# DB_MotherBoardConnectors.net
KiCad netlist of a schematic drawn in Altium Designer
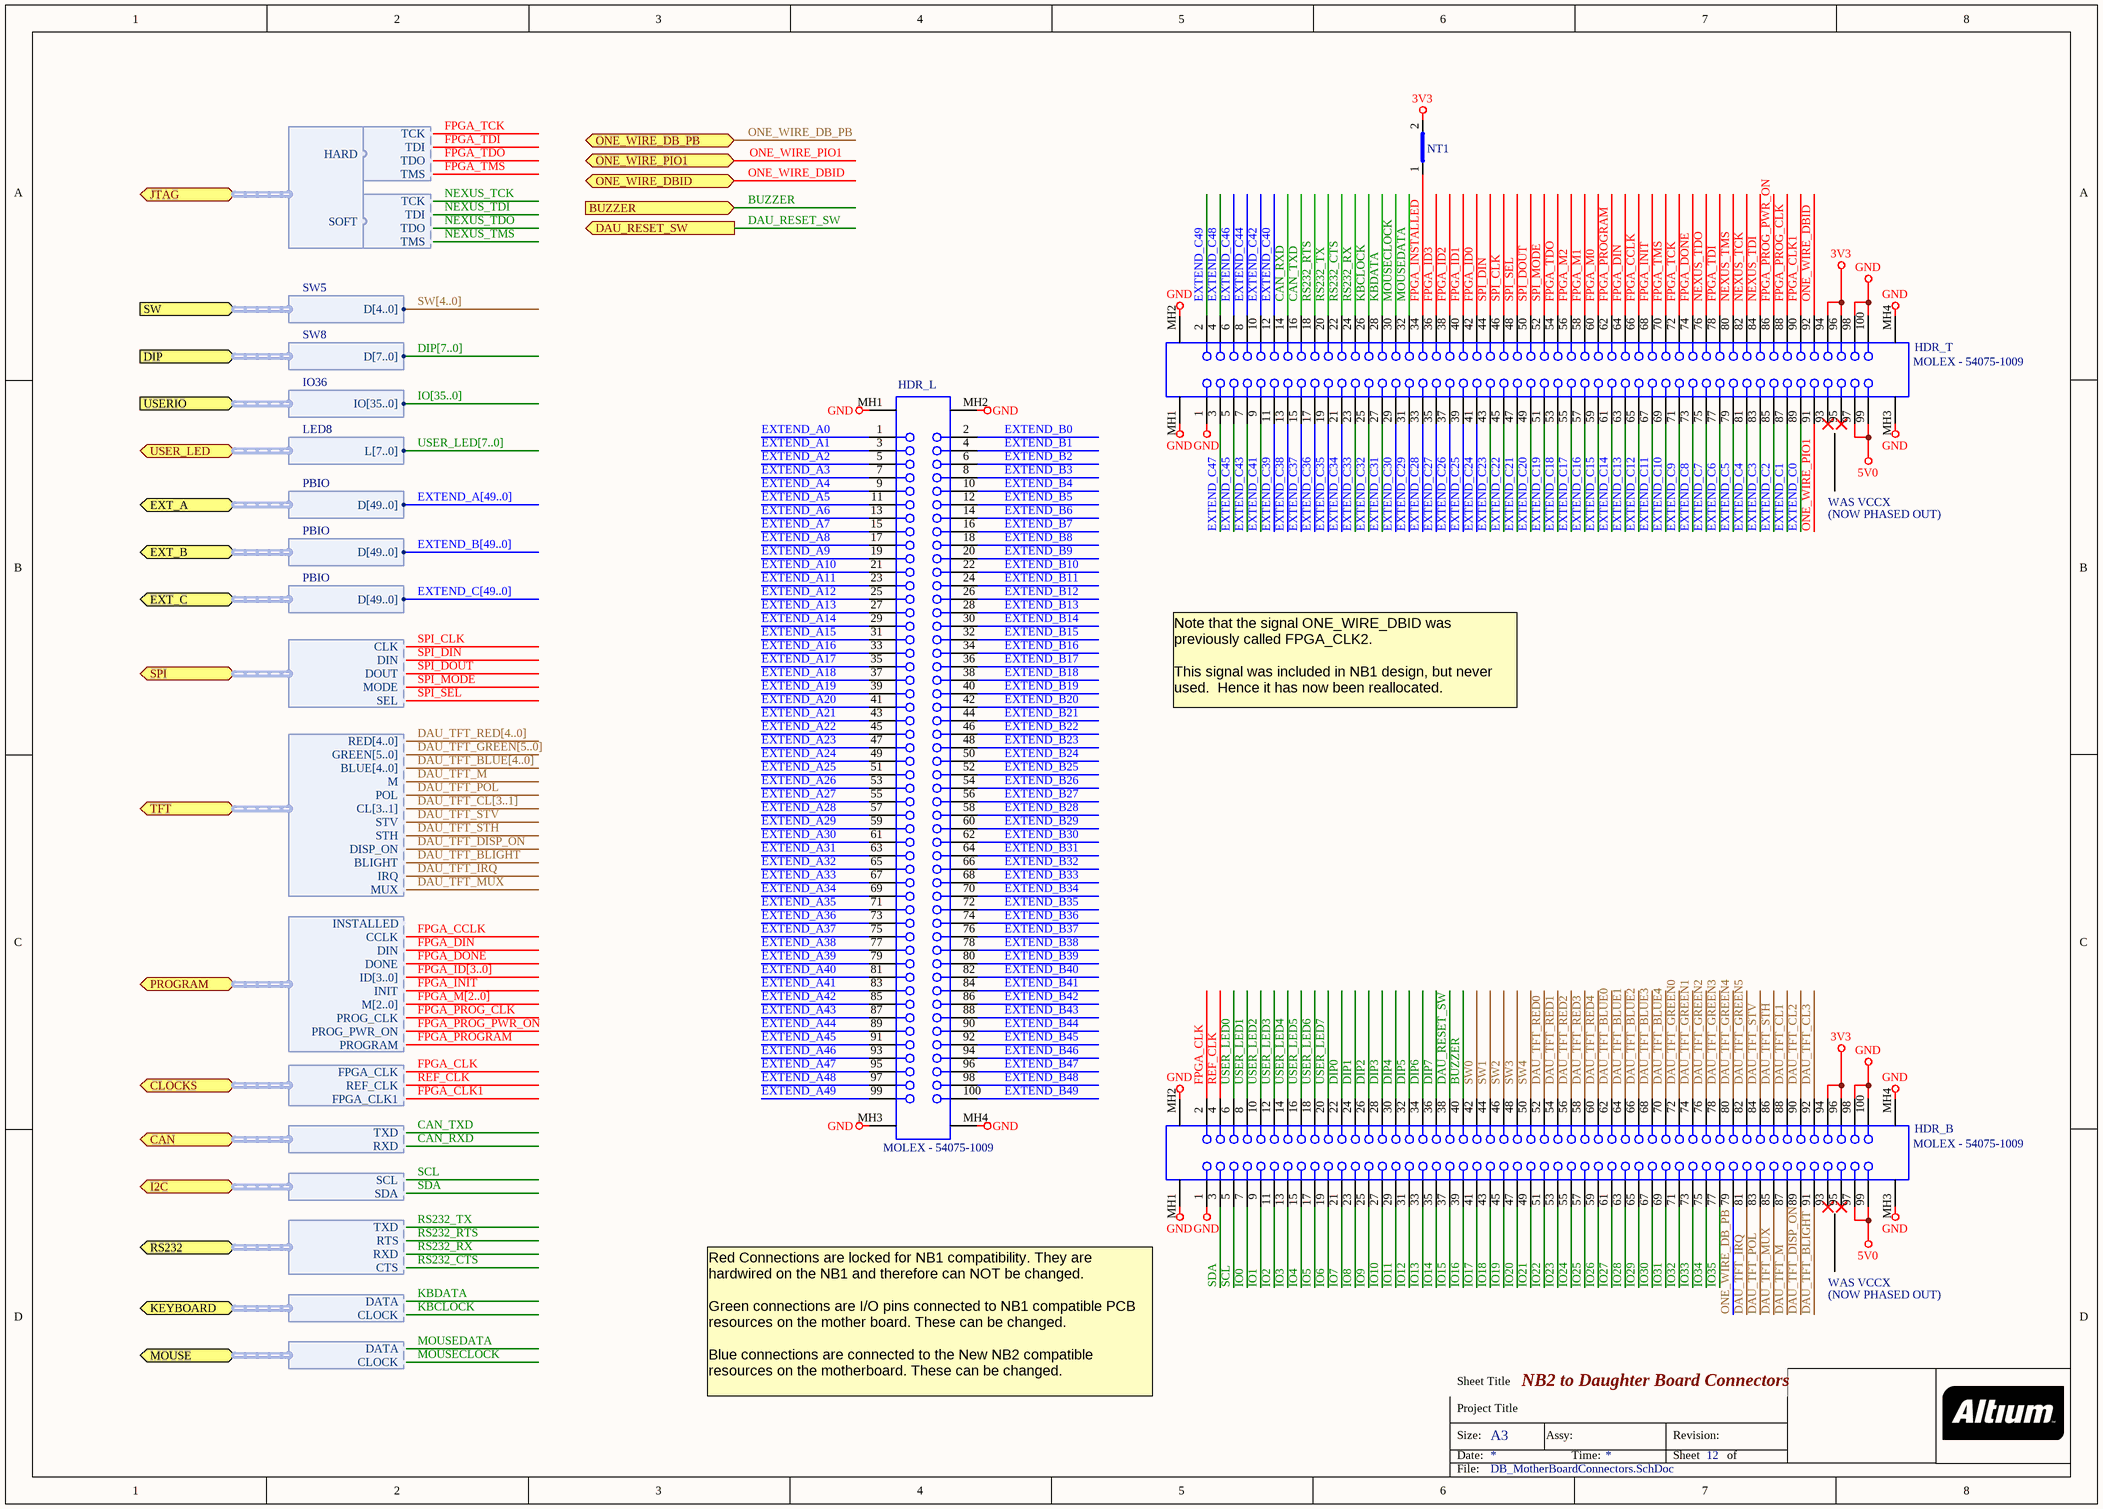
[diagram p0: DB_MotherBoardConnectors.SchDoc]

(export (version "E")
  (design (tool "Eeschema 10.0.6"))
  (components
    (comp (ref "HDR_B")
      (value "MOLEX - 54075-1009")
      (footprint "54075")
      (description "Connector, Molex Docking Station 100 Pin Male 54075")
      (libsource (lib "AltiumDesignLibrary") (part "CON-DOCKSTAT-100-M-STR"))
    )
    (comp (ref "HDR_L")
      (value "MOLEX - 54075-1009")
      (footprint "54075")
      (description "Connector, Molex Docking Station 100 Pin Male 54075")
      (libsource (lib "AltiumDesignLibrary") (part "CON-DOCKSTAT-100-M-STR"))
    )
    (comp (ref "HDR_T")
      (value "MOLEX - 54075-1009")
      (footprint "54075")
      (description "Connector, Molex Docking Station 100 Pin Male 54075")
      (libsource (lib "AltiumDesignLibrary") (part "CON-DOCKSTAT-100-M-STR"))
    )
    (comp (ref "NT1")
      (value "Net Tie SMT2")
      (footprint "NETTIE-SMT2-8X8")
      (description "Net-Tie, Surface Mount, 2 x 0.4mm x 0.2mm SMT Pads - For 0.2mm Track")
      (libsource (lib "AltiumDesignLibrary") (part "NETTIE-SMT2"))
    )
  )
  (nets
    (net (code "17") (name "/BUZZER") (class "Default")
      (node (ref "HDR_B") (pin "40") (pinfunction "40_40") (pintype "passive"))
    )
    (net (code "18") (name "/CAN_RXD") (class "Default")
      (node (ref "HDR_T") (pin "14") (pinfunction "14_14") (pintype "passive"))
    )
    (net (code "19") (name "/CAN_TXD") (class "Default")
      (node (ref "HDR_T") (pin "16") (pinfunction "16_16") (pintype "passive"))
    )
    (net (code "20") (name "/DAU_RESET_SW") (class "Default")
      (node (ref "HDR_B") (pin "38") (pinfunction "38_38") (pintype "passive"))
    )
    (net (code "21") (name "/DAU_TFT_BLIGHT") (class "Default")
      (node (ref "HDR_B") (pin "91") (pinfunction "91_91") (pintype "passive"))
    )
    (net (code "22") (name "/DAU_TFT_BLUE0") (class "Default")
      (node (ref "HDR_B") (pin "62") (pinfunction "62_62") (pintype "passive"))
    )
    (net (code "23") (name "/DAU_TFT_BLUE1") (class "Default")
      (node (ref "HDR_B") (pin "64") (pinfunction "64_64") (pintype "passive"))
    )
    (net (code "24") (name "/DAU_TFT_BLUE2") (class "Default")
      (node (ref "HDR_B") (pin "66") (pinfunction "66_66") (pintype "passive"))
    )
    (net (code "25") (name "/DAU_TFT_BLUE3") (class "Default")
      (node (ref "HDR_B") (pin "68") (pinfunction "68_68") (pintype "passive"))
    )
    (net (code "26") (name "/DAU_TFT_BLUE4") (class "Default")
      (node (ref "HDR_B") (pin "70") (pinfunction "70_70") (pintype "passive"))
    )
    (net (code "28") (name "/DAU_TFT_CL1") (class "Default")
      (node (ref "HDR_B") (pin "88") (pinfunction "88_88") (pintype "passive"))
    )
    (net (code "29") (name "/DAU_TFT_CL2") (class "Default")
      (node (ref "HDR_B") (pin "90") (pinfunction "90_90") (pintype "passive"))
    )
    (net (code "30") (name "/DAU_TFT_CL3") (class "Default")
      (node (ref "HDR_B") (pin "92") (pinfunction "92_92") (pintype "passive"))
    )
    (net (code "32") (name "/DAU_TFT_DISP_ON") (class "Default")
      (node (ref "HDR_B") (pin "89") (pinfunction "89_89") (pintype "passive"))
    )
    (net (code "33") (name "/DAU_TFT_GREEN0") (class "Default")
      (node (ref "HDR_B") (pin "72") (pinfunction "72_72") (pintype "passive"))
    )
    (net (code "34") (name "/DAU_TFT_GREEN1") (class "Default")
      (node (ref "HDR_B") (pin "74") (pinfunction "74_74") (pintype "passive"))
    )
    (net (code "35") (name "/DAU_TFT_GREEN2") (class "Default")
      (node (ref "HDR_B") (pin "76") (pinfunction "76_76") (pintype "passive"))
    )
    (net (code "36") (name "/DAU_TFT_GREEN3") (class "Default")
      (node (ref "HDR_B") (pin "78") (pinfunction "78_78") (pintype "passive"))
    )
    (net (code "37") (name "/DAU_TFT_GREEN4") (class "Default")
      (node (ref "HDR_B") (pin "80") (pinfunction "80_80") (pintype "passive"))
    )
    (net (code "38") (name "/DAU_TFT_GREEN5") (class "Default")
      (node (ref "HDR_B") (pin "82") (pinfunction "82_82") (pintype "passive"))
    )
    (net (code "40") (name "/DAU_TFT_IRQ") (class "Default")
      (node (ref "HDR_B") (pin "81") (pinfunction "81_81") (pintype "passive"))
    )
    (net (code "41") (name "/DAU_TFT_M") (class "Default")
      (node (ref "HDR_B") (pin "87") (pinfunction "87_87") (pintype "passive"))
    )
    (net (code "42") (name "/DAU_TFT_MUX") (class "Default")
      (node (ref "HDR_B") (pin "85") (pinfunction "85_85") (pintype "passive"))
    )
    (net (code "43") (name "/DAU_TFT_POL") (class "Default")
      (node (ref "HDR_B") (pin "83") (pinfunction "83_83") (pintype "passive"))
    )
    (net (code "44") (name "/DAU_TFT_RED0") (class "Default")
      (node (ref "HDR_B") (pin "52") (pinfunction "52_52") (pintype "passive"))
    )
    (net (code "45") (name "/DAU_TFT_RED1") (class "Default")
      (node (ref "HDR_B") (pin "54") (pinfunction "54_54") (pintype "passive"))
    )
    (net (code "46") (name "/DAU_TFT_RED2") (class "Default")
      (node (ref "HDR_B") (pin "56") (pinfunction "56_56") (pintype "passive"))
    )
    (net (code "47") (name "/DAU_TFT_RED3") (class "Default")
      (node (ref "HDR_B") (pin "58") (pinfunction "58_58") (pintype "passive"))
    )
    (net (code "48") (name "/DAU_TFT_RED4") (class "Default")
      (node (ref "HDR_B") (pin "60") (pinfunction "60_60") (pintype "passive"))
    )
    (net (code "50") (name "/DAU_TFT_STH") (class "Default")
      (node (ref "HDR_B") (pin "86") (pinfunction "86_86") (pintype "passive"))
    )
    (net (code "51") (name "/DAU_TFT_STV") (class "Default")
      (node (ref "HDR_B") (pin "84") (pinfunction "84_84") (pintype "passive"))
    )
    (net (code "52") (name "/DIP0") (class "Default")
      (node (ref "HDR_B") (pin "22") (pinfunction "22_22") (pintype "passive"))
    )
    (net (code "53") (name "/DIP1") (class "Default")
      (node (ref "HDR_B") (pin "24") (pinfunction "24_24") (pintype "passive"))
    )
    (net (code "54") (name "/DIP2") (class "Default")
      (node (ref "HDR_B") (pin "26") (pinfunction "26_26") (pintype "passive"))
    )
    (net (code "55") (name "/DIP3") (class "Default")
      (node (ref "HDR_B") (pin "28") (pinfunction "28_28") (pintype "passive"))
    )
    (net (code "56") (name "/DIP4") (class "Default")
      (node (ref "HDR_B") (pin "30") (pinfunction "30_30") (pintype "passive"))
    )
    (net (code "57") (name "/DIP5") (class "Default")
      (node (ref "HDR_B") (pin "32") (pinfunction "32_32") (pintype "passive"))
    )
    (net (code "58") (name "/DIP6") (class "Default")
      (node (ref "HDR_B") (pin "34") (pinfunction "34_34") (pintype "passive"))
    )
    (net (code "59") (name "/DIP7") (class "Default")
      (node (ref "HDR_B") (pin "36") (pinfunction "36_36") (pintype "passive"))
    )
    (net (code "61") (name "/EXTEND_A0") (class "Default")
      (node (ref "HDR_L") (pin "1") (pinfunction "1_1") (pintype "passive"))
    )
    (net (code "62") (name "/EXTEND_A1") (class "Default")
      (node (ref "HDR_L") (pin "3") (pinfunction "3_3") (pintype "passive"))
    )
    (net (code "63") (name "/EXTEND_A2") (class "Default")
      (node (ref "HDR_L") (pin "5") (pinfunction "5_5") (pintype "passive"))
    )
    (net (code "64") (name "/EXTEND_A3") (class "Default")
      (node (ref "HDR_L") (pin "7") (pinfunction "7_7") (pintype "passive"))
    )
    (net (code "65") (name "/EXTEND_A4") (class "Default")
      (node (ref "HDR_L") (pin "9") (pinfunction "9_9") (pintype "passive"))
    )
    (net (code "66") (name "/EXTEND_A5") (class "Default")
      (node (ref "HDR_L") (pin "11") (pinfunction "11_11") (pintype "passive"))
    )
    (net (code "67") (name "/EXTEND_A6") (class "Default")
      (node (ref "HDR_L") (pin "13") (pinfunction "13_13") (pintype "passive"))
    )
    (net (code "68") (name "/EXTEND_A7") (class "Default")
      (node (ref "HDR_L") (pin "15") (pinfunction "15_15") (pintype "passive"))
    )
    (net (code "69") (name "/EXTEND_A8") (class "Default")
      (node (ref "HDR_L") (pin "17") (pinfunction "17_17") (pintype "passive"))
    )
    (net (code "70") (name "/EXTEND_A9") (class "Default")
      (node (ref "HDR_L") (pin "19") (pinfunction "19_19") (pintype "passive"))
    )
    (net (code "71") (name "/EXTEND_A10") (class "Default")
      (node (ref "HDR_L") (pin "21") (pinfunction "21_21") (pintype "passive"))
    )
    (net (code "72") (name "/EXTEND_A11") (class "Default")
      (node (ref "HDR_L") (pin "23") (pinfunction "23_23") (pintype "passive"))
    )
    (net (code "73") (name "/EXTEND_A12") (class "Default")
      (node (ref "HDR_L") (pin "25") (pinfunction "25_25") (pintype "passive"))
    )
    (net (code "74") (name "/EXTEND_A13") (class "Default")
      (node (ref "HDR_L") (pin "27") (pinfunction "27_27") (pintype "passive"))
    )
    (net (code "75") (name "/EXTEND_A14") (class "Default")
      (node (ref "HDR_L") (pin "29") (pinfunction "29_29") (pintype "passive"))
    )
    (net (code "76") (name "/EXTEND_A15") (class "Default")
      (node (ref "HDR_L") (pin "31") (pinfunction "31_31") (pintype "passive"))
    )
    (net (code "77") (name "/EXTEND_A16") (class "Default")
      (node (ref "HDR_L") (pin "33") (pinfunction "33_33") (pintype "passive"))
    )
    (net (code "78") (name "/EXTEND_A17") (class "Default")
      (node (ref "HDR_L") (pin "35") (pinfunction "35_35") (pintype "passive"))
    )
    (net (code "79") (name "/EXTEND_A18") (class "Default")
      (node (ref "HDR_L") (pin "37") (pinfunction "37_37") (pintype "passive"))
    )
    (net (code "80") (name "/EXTEND_A19") (class "Default")
      (node (ref "HDR_L") (pin "39") (pinfunction "39_39") (pintype "passive"))
    )
    (net (code "81") (name "/EXTEND_A20") (class "Default")
      (node (ref "HDR_L") (pin "41") (pinfunction "41_41") (pintype "passive"))
    )
    (net (code "82") (name "/EXTEND_A21") (class "Default")
      (node (ref "HDR_L") (pin "43") (pinfunction "43_43") (pintype "passive"))
    )
    (net (code "83") (name "/EXTEND_A22") (class "Default")
      (node (ref "HDR_L") (pin "45") (pinfunction "45_45") (pintype "passive"))
    )
    (net (code "84") (name "/EXTEND_A23") (class "Default")
      (node (ref "HDR_L") (pin "47") (pinfunction "47_47") (pintype "passive"))
    )
    (net (code "85") (name "/EXTEND_A24") (class "Default")
      (node (ref "HDR_L") (pin "49") (pinfunction "49_49") (pintype "passive"))
    )
    (net (code "86") (name "/EXTEND_A25") (class "Default")
      (node (ref "HDR_L") (pin "51") (pinfunction "51_51") (pintype "passive"))
    )
    (net (code "87") (name "/EXTEND_A26") (class "Default")
      (node (ref "HDR_L") (pin "53") (pinfunction "53_53") (pintype "passive"))
    )
    (net (code "88") (name "/EXTEND_A27") (class "Default")
      (node (ref "HDR_L") (pin "55") (pinfunction "55_55") (pintype "passive"))
    )
    (net (code "89") (name "/EXTEND_A28") (class "Default")
      (node (ref "HDR_L") (pin "57") (pinfunction "57_57") (pintype "passive"))
    )
    (net (code "90") (name "/EXTEND_A29") (class "Default")
      (node (ref "HDR_L") (pin "59") (pinfunction "59_59") (pintype "passive"))
    )
    (net (code "91") (name "/EXTEND_A30") (class "Default")
      (node (ref "HDR_L") (pin "61") (pinfunction "61_61") (pintype "passive"))
    )
    (net (code "92") (name "/EXTEND_A31") (class "Default")
      (node (ref "HDR_L") (pin "63") (pinfunction "63_63") (pintype "passive"))
    )
    (net (code "93") (name "/EXTEND_A32") (class "Default")
      (node (ref "HDR_L") (pin "65") (pinfunction "65_65") (pintype "passive"))
    )
    (net (code "94") (name "/EXTEND_A33") (class "Default")
      (node (ref "HDR_L") (pin "67") (pinfunction "67_67") (pintype "passive"))
    )
    (net (code "95") (name "/EXTEND_A34") (class "Default")
      (node (ref "HDR_L") (pin "69") (pinfunction "69_69") (pintype "passive"))
    )
    (net (code "96") (name "/EXTEND_A35") (class "Default")
      (node (ref "HDR_L") (pin "71") (pinfunction "71_71") (pintype "passive"))
    )
    (net (code "97") (name "/EXTEND_A36") (class "Default")
      (node (ref "HDR_L") (pin "73") (pinfunction "73_73") (pintype "passive"))
    )
    (net (code "98") (name "/EXTEND_A37") (class "Default")
      (node (ref "HDR_L") (pin "75") (pinfunction "75_75") (pintype "passive"))
    )
    (net (code "99") (name "/EXTEND_A38") (class "Default")
      (node (ref "HDR_L") (pin "77") (pinfunction "77_77") (pintype "passive"))
    )
    (net (code "100") (name "/EXTEND_A39") (class "Default")
      (node (ref "HDR_L") (pin "79") (pinfunction "79_79") (pintype "passive"))
    )
    (net (code "101") (name "/EXTEND_A40") (class "Default")
      (node (ref "HDR_L") (pin "81") (pinfunction "81_81") (pintype "passive"))
    )
    (net (code "102") (name "/EXTEND_A41") (class "Default")
      (node (ref "HDR_L") (pin "83") (pinfunction "83_83") (pintype "passive"))
    )
    (net (code "103") (name "/EXTEND_A42") (class "Default")
      (node (ref "HDR_L") (pin "85") (pinfunction "85_85") (pintype "passive"))
    )
    (net (code "104") (name "/EXTEND_A43") (class "Default")
      (node (ref "HDR_L") (pin "87") (pinfunction "87_87") (pintype "passive"))
    )
    (net (code "105") (name "/EXTEND_A44") (class "Default")
      (node (ref "HDR_L") (pin "89") (pinfunction "89_89") (pintype "passive"))
    )
    (net (code "106") (name "/EXTEND_A45") (class "Default")
      (node (ref "HDR_L") (pin "91") (pinfunction "91_91") (pintype "passive"))
    )
    (net (code "107") (name "/EXTEND_A46") (class "Default")
      (node (ref "HDR_L") (pin "93") (pinfunction "93_93") (pintype "passive"))
    )
    (net (code "108") (name "/EXTEND_A47") (class "Default")
      (node (ref "HDR_L") (pin "95") (pinfunction "95_95") (pintype "passive"))
    )
    (net (code "109") (name "/EXTEND_A48") (class "Default")
      (node (ref "HDR_L") (pin "97") (pinfunction "97_97") (pintype "passive"))
    )
    (net (code "110") (name "/EXTEND_A49") (class "Default")
      (node (ref "HDR_L") (pin "99") (pinfunction "99_99") (pintype "passive"))
    )
    (net (code "111") (name "/EXTEND_B0") (class "Default")
      (node (ref "HDR_L") (pin "2") (pinfunction "2_2") (pintype "passive"))
    )
    (net (code "112") (name "/EXTEND_B1") (class "Default")
      (node (ref "HDR_L") (pin "4") (pinfunction "4_4") (pintype "passive"))
    )
    (net (code "113") (name "/EXTEND_B2") (class "Default")
      (node (ref "HDR_L") (pin "6") (pinfunction "6_6") (pintype "passive"))
    )
    (net (code "114") (name "/EXTEND_B3") (class "Default")
      (node (ref "HDR_L") (pin "8") (pinfunction "8_8") (pintype "passive"))
    )
    (net (code "115") (name "/EXTEND_B4") (class "Default")
      (node (ref "HDR_L") (pin "10") (pinfunction "10_10") (pintype "passive"))
    )
    (net (code "116") (name "/EXTEND_B5") (class "Default")
      (node (ref "HDR_L") (pin "12") (pinfunction "12_12") (pintype "passive"))
    )
    (net (code "117") (name "/EXTEND_B6") (class "Default")
      (node (ref "HDR_L") (pin "14") (pinfunction "14_14") (pintype "passive"))
    )
    (net (code "118") (name "/EXTEND_B7") (class "Default")
      (node (ref "HDR_L") (pin "16") (pinfunction "16_16") (pintype "passive"))
    )
    (net (code "119") (name "/EXTEND_B8") (class "Default")
      (node (ref "HDR_L") (pin "18") (pinfunction "18_18") (pintype "passive"))
    )
    (net (code "120") (name "/EXTEND_B9") (class "Default")
      (node (ref "HDR_L") (pin "20") (pinfunction "20_20") (pintype "passive"))
    )
    (net (code "121") (name "/EXTEND_B10") (class "Default")
      (node (ref "HDR_L") (pin "22") (pinfunction "22_22") (pintype "passive"))
    )
    (net (code "122") (name "/EXTEND_B11") (class "Default")
      (node (ref "HDR_L") (pin "24") (pinfunction "24_24") (pintype "passive"))
    )
    (net (code "123") (name "/EXTEND_B12") (class "Default")
      (node (ref "HDR_L") (pin "26") (pinfunction "26_26") (pintype "passive"))
    )
    (net (code "124") (name "/EXTEND_B13") (class "Default")
      (node (ref "HDR_L") (pin "28") (pinfunction "28_28") (pintype "passive"))
    )
    (net (code "125") (name "/EXTEND_B14") (class "Default")
      (node (ref "HDR_L") (pin "30") (pinfunction "30_30") (pintype "passive"))
    )
    (net (code "126") (name "/EXTEND_B15") (class "Default")
      (node (ref "HDR_L") (pin "32") (pinfunction "32_32") (pintype "passive"))
    )
    (net (code "127") (name "/EXTEND_B16") (class "Default")
      (node (ref "HDR_L") (pin "34") (pinfunction "34_34") (pintype "passive"))
    )
    (net (code "128") (name "/EXTEND_B17") (class "Default")
      (node (ref "HDR_L") (pin "36") (pinfunction "36_36") (pintype "passive"))
    )
    (net (code "129") (name "/EXTEND_B18") (class "Default")
      (node (ref "HDR_L") (pin "38") (pinfunction "38_38") (pintype "passive"))
    )
    (net (code "130") (name "/EXTEND_B19") (class "Default")
      (node (ref "HDR_L") (pin "40") (pinfunction "40_40") (pintype "passive"))
    )
    (net (code "131") (name "/EXTEND_B20") (class "Default")
      (node (ref "HDR_L") (pin "42") (pinfunction "42_42") (pintype "passive"))
    )
    (net (code "132") (name "/EXTEND_B21") (class "Default")
      (node (ref "HDR_L") (pin "44") (pinfunction "44_44") (pintype "passive"))
    )
    (net (code "133") (name "/EXTEND_B22") (class "Default")
      (node (ref "HDR_L") (pin "46") (pinfunction "46_46") (pintype "passive"))
    )
    (net (code "134") (name "/EXTEND_B23") (class "Default")
      (node (ref "HDR_L") (pin "48") (pinfunction "48_48") (pintype "passive"))
    )
    (net (code "135") (name "/EXTEND_B24") (class "Default")
      (node (ref "HDR_L") (pin "50") (pinfunction "50_50") (pintype "passive"))
    )
    (net (code "136") (name "/EXTEND_B25") (class "Default")
      (node (ref "HDR_L") (pin "52") (pinfunction "52_52") (pintype "passive"))
    )
    (net (code "137") (name "/EXTEND_B26") (class "Default")
      (node (ref "HDR_L") (pin "54") (pinfunction "54_54") (pintype "passive"))
    )
    (net (code "138") (name "/EXTEND_B27") (class "Default")
      (node (ref "HDR_L") (pin "56") (pinfunction "56_56") (pintype "passive"))
    )
    (net (code "139") (name "/EXTEND_B28") (class "Default")
      (node (ref "HDR_L") (pin "58") (pinfunction "58_58") (pintype "passive"))
    )
    (net (code "140") (name "/EXTEND_B29") (class "Default")
      (node (ref "HDR_L") (pin "60") (pinfunction "60_60") (pintype "passive"))
    )
    (net (code "141") (name "/EXTEND_B30") (class "Default")
      (node (ref "HDR_L") (pin "62") (pinfunction "62_62") (pintype "passive"))
    )
    (net (code "142") (name "/EXTEND_B31") (class "Default")
      (node (ref "HDR_L") (pin "64") (pinfunction "64_64") (pintype "passive"))
    )
    (net (code "143") (name "/EXTEND_B32") (class "Default")
      (node (ref "HDR_L") (pin "66") (pinfunction "66_66") (pintype "passive"))
    )
    (net (code "144") (name "/EXTEND_B33") (class "Default")
      (node (ref "HDR_L") (pin "68") (pinfunction "68_68") (pintype "passive"))
    )
    (net (code "145") (name "/EXTEND_B34") (class "Default")
      (node (ref "HDR_L") (pin "70") (pinfunction "70_70") (pintype "passive"))
    )
    (net (code "146") (name "/EXTEND_B35") (class "Default")
      (node (ref "HDR_L") (pin "72") (pinfunction "72_72") (pintype "passive"))
    )
    (net (code "147") (name "/EXTEND_B36") (class "Default")
      (node (ref "HDR_L") (pin "74") (pinfunction "74_74") (pintype "passive"))
    )
    (net (code "148") (name "/EXTEND_B37") (class "Default")
      (node (ref "HDR_L") (pin "76") (pinfunction "76_76") (pintype "passive"))
    )
    (net (code "149") (name "/EXTEND_B38") (class "Default")
      (node (ref "HDR_L") (pin "78") (pinfunction "78_78") (pintype "passive"))
    )
    (net (code "150") (name "/EXTEND_B39") (class "Default")
      (node (ref "HDR_L") (pin "80") (pinfunction "80_80") (pintype "passive"))
    )
    (net (code "151") (name "/EXTEND_B40") (class "Default")
      (node (ref "HDR_L") (pin "82") (pinfunction "82_82") (pintype "passive"))
    )
    (net (code "152") (name "/EXTEND_B41") (class "Default")
      (node (ref "HDR_L") (pin "84") (pinfunction "84_84") (pintype "passive"))
    )
    (net (code "153") (name "/EXTEND_B42") (class "Default")
      (node (ref "HDR_L") (pin "86") (pinfunction "86_86") (pintype "passive"))
    )
    (net (code "154") (name "/EXTEND_B43") (class "Default")
      (node (ref "HDR_L") (pin "88") (pinfunction "88_88") (pintype "passive"))
    )
    (net (code "155") (name "/EXTEND_B44") (class "Default")
      (node (ref "HDR_L") (pin "90") (pinfunction "90_90") (pintype "passive"))
    )
    (net (code "156") (name "/EXTEND_B45") (class "Default")
      (node (ref "HDR_L") (pin "92") (pinfunction "92_92") (pintype "passive"))
    )
    (net (code "157") (name "/EXTEND_B46") (class "Default")
      (node (ref "HDR_L") (pin "94") (pinfunction "94_94") (pintype "passive"))
    )
    (net (code "158") (name "/EXTEND_B47") (class "Default")
      (node (ref "HDR_L") (pin "96") (pinfunction "96_96") (pintype "passive"))
    )
    (net (code "159") (name "/EXTEND_B48") (class "Default")
      (node (ref "HDR_L") (pin "98") (pinfunction "98_98") (pintype "passive"))
    )
    (net (code "160") (name "/EXTEND_B49") (class "Default")
      (node (ref "HDR_L") (pin "100") (pinfunction "100_100") (pintype "passive"))
    )
    (net (code "161") (name "/EXTEND_C0") (class "Default")
      (node (ref "HDR_T") (pin "89") (pinfunction "89_89") (pintype "passive"))
    )
    (net (code "162") (name "/EXTEND_C1") (class "Default")
      (node (ref "HDR_T") (pin "87") (pinfunction "87_87") (pintype "passive"))
    )
    (net (code "163") (name "/EXTEND_C2") (class "Default")
      (node (ref "HDR_T") (pin "85") (pinfunction "85_85") (pintype "passive"))
    )
    (net (code "164") (name "/EXTEND_C3") (class "Default")
      (node (ref "HDR_T") (pin "83") (pinfunction "83_83") (pintype "passive"))
    )
    (net (code "165") (name "/EXTEND_C4") (class "Default")
      (node (ref "HDR_T") (pin "81") (pinfunction "81_81") (pintype "passive"))
    )
    (net (code "166") (name "/EXTEND_C5") (class "Default")
      (node (ref "HDR_T") (pin "79") (pinfunction "79_79") (pintype "passive"))
    )
    (net (code "167") (name "/EXTEND_C6") (class "Default")
      (node (ref "HDR_T") (pin "77") (pinfunction "77_77") (pintype "passive"))
    )
    (net (code "168") (name "/EXTEND_C7") (class "Default")
      (node (ref "HDR_T") (pin "75") (pinfunction "75_75") (pintype "passive"))
    )
    (net (code "169") (name "/EXTEND_C8") (class "Default")
      (node (ref "HDR_T") (pin "73") (pinfunction "73_73") (pintype "passive"))
    )
    (net (code "170") (name "/EXTEND_C9") (class "Default")
      (node (ref "HDR_T") (pin "71") (pinfunction "71_71") (pintype "passive"))
    )
    (net (code "171") (name "/EXTEND_C10") (class "Default")
      (node (ref "HDR_T") (pin "69") (pinfunction "69_69") (pintype "passive"))
    )
    (net (code "172") (name "/EXTEND_C11") (class "Default")
      (node (ref "HDR_T") (pin "67") (pinfunction "67_67") (pintype "passive"))
    )
    (net (code "173") (name "/EXTEND_C12") (class "Default")
      (node (ref "HDR_T") (pin "65") (pinfunction "65_65") (pintype "passive"))
    )
    (net (code "174") (name "/EXTEND_C13") (class "Default")
      (node (ref "HDR_T") (pin "63") (pinfunction "63_63") (pintype "passive"))
    )
    (net (code "175") (name "/EXTEND_C14") (class "Default")
      (node (ref "HDR_T") (pin "61") (pinfunction "61_61") (pintype "passive"))
    )
    (net (code "176") (name "/EXTEND_C15") (class "Default")
      (node (ref "HDR_T") (pin "59") (pinfunction "59_59") (pintype "passive"))
    )
    (net (code "177") (name "/EXTEND_C16") (class "Default")
      (node (ref "HDR_T") (pin "57") (pinfunction "57_57") (pintype "passive"))
    )
    (net (code "178") (name "/EXTEND_C17") (class "Default")
      (node (ref "HDR_T") (pin "55") (pinfunction "55_55") (pintype "passive"))
    )
    (net (code "179") (name "/EXTEND_C18") (class "Default")
      (node (ref "HDR_T") (pin "53") (pinfunction "53_53") (pintype "passive"))
    )
    (net (code "180") (name "/EXTEND_C19") (class "Default")
      (node (ref "HDR_T") (pin "51") (pinfunction "51_51") (pintype "passive"))
    )
    (net (code "181") (name "/EXTEND_C20") (class "Default")
      (node (ref "HDR_T") (pin "49") (pinfunction "49_49") (pintype "passive"))
    )
    (net (code "182") (name "/EXTEND_C21") (class "Default")
      (node (ref "HDR_T") (pin "47") (pinfunction "47_47") (pintype "passive"))
    )
    (net (code "183") (name "/EXTEND_C22") (class "Default")
      (node (ref "HDR_T") (pin "45") (pinfunction "45_45") (pintype "passive"))
    )
    (net (code "184") (name "/EXTEND_C23") (class "Default")
      (node (ref "HDR_T") (pin "43") (pinfunction "43_43") (pintype "passive"))
    )
    (net (code "185") (name "/EXTEND_C24") (class "Default")
      (node (ref "HDR_T") (pin "41") (pinfunction "41_41") (pintype "passive"))
    )
    (net (code "186") (name "/EXTEND_C25") (class "Default")
      (node (ref "HDR_T") (pin "39") (pinfunction "39_39") (pintype "passive"))
    )
    (net (code "187") (name "/EXTEND_C26") (class "Default")
      (node (ref "HDR_T") (pin "37") (pinfunction "37_37") (pintype "passive"))
    )
    (net (code "188") (name "/EXTEND_C27") (class "Default")
      (node (ref "HDR_T") (pin "35") (pinfunction "35_35") (pintype "passive"))
    )
    (net (code "189") (name "/EXTEND_C28") (class "Default")
      (node (ref "HDR_T") (pin "33") (pinfunction "33_33") (pintype "passive"))
    )
    (net (code "190") (name "/EXTEND_C29") (class "Default")
      (node (ref "HDR_T") (pin "31") (pinfunction "31_31") (pintype "passive"))
    )
    (net (code "191") (name "/EXTEND_C30") (class "Default")
      (node (ref "HDR_T") (pin "29") (pinfunction "29_29") (pintype "passive"))
    )
    (net (code "192") (name "/EXTEND_C31") (class "Default")
      (node (ref "HDR_T") (pin "27") (pinfunction "27_27") (pintype "passive"))
    )
    (net (code "193") (name "/EXTEND_C32") (class "Default")
      (node (ref "HDR_T") (pin "25") (pinfunction "25_25") (pintype "passive"))
    )
    (net (code "194") (name "/EXTEND_C33") (class "Default")
      (node (ref "HDR_T") (pin "23") (pinfunction "23_23") (pintype "passive"))
    )
    (net (code "195") (name "/EXTEND_C34") (class "Default")
      (node (ref "HDR_T") (pin "21") (pinfunction "21_21") (pintype "passive"))
    )
    (net (code "196") (name "/EXTEND_C35") (class "Default")
      (node (ref "HDR_T") (pin "19") (pinfunction "19_19") (pintype "passive"))
    )
    (net (code "197") (name "/EXTEND_C36") (class "Default")
      (node (ref "HDR_T") (pin "17") (pinfunction "17_17") (pintype "passive"))
    )
    (net (code "198") (name "/EXTEND_C37") (class "Default")
      (node (ref "HDR_T") (pin "15") (pinfunction "15_15") (pintype "passive"))
    )
    (net (code "199") (name "/EXTEND_C38") (class "Default")
      (node (ref "HDR_T") (pin "13") (pinfunction "13_13") (pintype "passive"))
    )
    (net (code "200") (name "/EXTEND_C39") (class "Default")
      (node (ref "HDR_T") (pin "11") (pinfunction "11_11") (pintype "passive"))
    )
    (net (code "201") (name "/EXTEND_C40") (class "Default")
      (node (ref "HDR_T") (pin "12") (pinfunction "12_12") (pintype "passive"))
    )
    (net (code "202") (name "/EXTEND_C41") (class "Default")
      (node (ref "HDR_T") (pin "9") (pinfunction "9_9") (pintype "passive"))
    )
    (net (code "203") (name "/EXTEND_C42") (class "Default")
      (node (ref "HDR_T") (pin "10") (pinfunction "10_10") (pintype "passive"))
    )
    (net (code "204") (name "/EXTEND_C43") (class "Default")
      (node (ref "HDR_T") (pin "7") (pinfunction "7_7") (pintype "passive"))
    )
    (net (code "205") (name "/EXTEND_C44") (class "Default")
      (node (ref "HDR_T") (pin "8") (pinfunction "8_8") (pintype "passive"))
    )
    (net (code "206") (name "/EXTEND_C45") (class "Default")
      (node (ref "HDR_T") (pin "5") (pinfunction "5_5") (pintype "passive"))
    )
    (net (code "207") (name "/EXTEND_C46") (class "Default")
      (node (ref "HDR_T") (pin "6") (pinfunction "6_6") (pintype "passive"))
    )
    (net (code "208") (name "/EXTEND_C47") (class "Default")
      (node (ref "HDR_T") (pin "3") (pinfunction "3_3") (pintype "passive"))
    )
    (net (code "209") (name "/EXTEND_C48") (class "Default")
      (node (ref "HDR_T") (pin "4") (pinfunction "4_4") (pintype "passive"))
    )
    (net (code "210") (name "/EXTEND_C49") (class "Default")
      (node (ref "HDR_T") (pin "2") (pinfunction "2_2") (pintype "passive"))
    )
    (net (code "214") (name "/FPGA_CCLK") (class "Default")
      (node (ref "HDR_T") (pin "66") (pinfunction "66_66") (pintype "passive"))
    )
    (net (code "215") (name "/FPGA_CLK") (class "Default")
      (node (ref "HDR_B") (pin "2") (pinfunction "2_2") (pintype "passive"))
    )
    (net (code "216") (name "/FPGA_CLK1") (class "Default")
      (node (ref "HDR_T") (pin "90") (pinfunction "90_90") (pintype "passive"))
    )
    (net (code "217") (name "/FPGA_DIN") (class "Default")
      (node (ref "HDR_T") (pin "64") (pinfunction "64_64") (pintype "passive"))
    )
    (net (code "218") (name "/FPGA_DONE") (class "Default")
      (node (ref "HDR_T") (pin "74") (pinfunction "74_74") (pintype "passive"))
    )
    (net (code "219") (name "/FPGA_ID0") (class "Default")
      (node (ref "HDR_T") (pin "42") (pinfunction "42_42") (pintype "passive"))
    )
    (net (code "220") (name "/FPGA_ID1") (class "Default")
      (node (ref "HDR_T") (pin "40") (pinfunction "40_40") (pintype "passive"))
    )
    (net (code "221") (name "/FPGA_ID2") (class "Default")
      (node (ref "HDR_T") (pin "38") (pinfunction "38_38") (pintype "passive"))
    )
    (net (code "222") (name "/FPGA_ID3") (class "Default")
      (node (ref "HDR_T") (pin "36") (pinfunction "36_36") (pintype "passive"))
    )
    (net (code "224") (name "/FPGA_INIT") (class "Default")
      (node (ref "HDR_T") (pin "68") (pinfunction "68_68") (pintype "passive"))
    )
    (net (code "225") (name "/FPGA_INSTALLED") (class "Default")
      (node (ref "HDR_T") (pin "34") (pinfunction "34_34") (pintype "passive"))
      (node (ref "NT1") (pin "1") (pinfunction "Net1_1") (pintype "passive"))
    )
    (net (code "226") (name "/FPGA_M0") (class "Default")
      (node (ref "HDR_T") (pin "60") (pinfunction "60_60") (pintype "passive"))
    )
    (net (code "227") (name "/FPGA_M1") (class "Default")
      (node (ref "HDR_T") (pin "58") (pinfunction "58_58") (pintype "passive"))
    )
    (net (code "228") (name "/FPGA_M2") (class "Default")
      (node (ref "HDR_T") (pin "56") (pinfunction "56_56") (pintype "passive"))
    )
    (net (code "230") (name "/FPGA_PROGRAM") (class "Default")
      (node (ref "HDR_T") (pin "62") (pinfunction "62_62") (pintype "passive"))
    )
    (net (code "231") (name "/FPGA_PROG_CLK") (class "Default")
      (node (ref "HDR_T") (pin "88") (pinfunction "88_88") (pintype "passive"))
    )
    (net (code "232") (name "/FPGA_PROG_PWR_ON") (class "Default")
      (node (ref "HDR_T") (pin "86") (pinfunction "86_86") (pintype "passive"))
    )
    (net (code "233") (name "/FPGA_TCK") (class "Default")
      (node (ref "HDR_T") (pin "72") (pinfunction "72_72") (pintype "passive"))
    )
    (net (code "234") (name "/FPGA_TDI") (class "Default")
      (node (ref "HDR_T") (pin "78") (pinfunction "78_78") (pintype "passive"))
    )
    (net (code "235") (name "/FPGA_TDO") (class "Default")
      (node (ref "HDR_T") (pin "54") (pinfunction "54_54") (pintype "passive"))
    )
    (net (code "236") (name "/FPGA_TMS") (class "Default")
      (node (ref "HDR_T") (pin "70") (pinfunction "70_70") (pintype "passive"))
    )
    (net (code "237") (name "/IO0") (class "Default")
      (node (ref "HDR_B") (pin "7") (pinfunction "7_7") (pintype "passive"))
    )
    (net (code "238") (name "/IO1") (class "Default")
      (node (ref "HDR_B") (pin "9") (pinfunction "9_9") (pintype "passive"))
    )
    (net (code "239") (name "/IO2") (class "Default")
      (node (ref "HDR_B") (pin "11") (pinfunction "11_11") (pintype "passive"))
    )
    (net (code "240") (name "/IO3") (class "Default")
      (node (ref "HDR_B") (pin "13") (pinfunction "13_13") (pintype "passive"))
    )
    (net (code "241") (name "/IO4") (class "Default")
      (node (ref "HDR_B") (pin "15") (pinfunction "15_15") (pintype "passive"))
    )
    (net (code "242") (name "/IO5") (class "Default")
      (node (ref "HDR_B") (pin "17") (pinfunction "17_17") (pintype "passive"))
    )
    (net (code "243") (name "/IO6") (class "Default")
      (node (ref "HDR_B") (pin "19") (pinfunction "19_19") (pintype "passive"))
    )
    (net (code "244") (name "/IO7") (class "Default")
      (node (ref "HDR_B") (pin "21") (pinfunction "21_21") (pintype "passive"))
    )
    (net (code "245") (name "/IO8") (class "Default")
      (node (ref "HDR_B") (pin "23") (pinfunction "23_23") (pintype "passive"))
    )
    (net (code "246") (name "/IO9") (class "Default")
      (node (ref "HDR_B") (pin "25") (pinfunction "25_25") (pintype "passive"))
    )
    (net (code "247") (name "/IO10") (class "Default")
      (node (ref "HDR_B") (pin "27") (pinfunction "27_27") (pintype "passive"))
    )
    (net (code "248") (name "/IO11") (class "Default")
      (node (ref "HDR_B") (pin "29") (pinfunction "29_29") (pintype "passive"))
    )
    (net (code "249") (name "/IO12") (class "Default")
      (node (ref "HDR_B") (pin "31") (pinfunction "31_31") (pintype "passive"))
    )
    (net (code "250") (name "/IO13") (class "Default")
      (node (ref "HDR_B") (pin "33") (pinfunction "33_33") (pintype "passive"))
    )
    (net (code "251") (name "/IO14") (class "Default")
      (node (ref "HDR_B") (pin "35") (pinfunction "35_35") (pintype "passive"))
    )
    (net (code "252") (name "/IO15") (class "Default")
      (node (ref "HDR_B") (pin "37") (pinfunction "37_37") (pintype "passive"))
    )
    (net (code "253") (name "/IO16") (class "Default")
      (node (ref "HDR_B") (pin "39") (pinfunction "39_39") (pintype "passive"))
    )
    (net (code "254") (name "/IO17") (class "Default")
      (node (ref "HDR_B") (pin "41") (pinfunction "41_41") (pintype "passive"))
    )
    (net (code "255") (name "/IO18") (class "Default")
      (node (ref "HDR_B") (pin "43") (pinfunction "43_43") (pintype "passive"))
    )
    (net (code "256") (name "/IO19") (class "Default")
      (node (ref "HDR_B") (pin "45") (pinfunction "45_45") (pintype "passive"))
    )
    (net (code "257") (name "/IO20") (class "Default")
      (node (ref "HDR_B") (pin "47") (pinfunction "47_47") (pintype "passive"))
    )
    (net (code "258") (name "/IO21") (class "Default")
      (node (ref "HDR_B") (pin "49") (pinfunction "49_49") (pintype "passive"))
    )
    (net (code "259") (name "/IO22") (class "Default")
      (node (ref "HDR_B") (pin "51") (pinfunction "51_51") (pintype "passive"))
    )
    (net (code "260") (name "/IO23") (class "Default")
      (node (ref "HDR_B") (pin "53") (pinfunction "53_53") (pintype "passive"))
    )
    (net (code "261") (name "/IO24") (class "Default")
      (node (ref "HDR_B") (pin "55") (pinfunction "55_55") (pintype "passive"))
    )
    (net (code "262") (name "/IO25") (class "Default")
      (node (ref "HDR_B") (pin "57") (pinfunction "57_57") (pintype "passive"))
    )
    (net (code "263") (name "/IO26") (class "Default")
      (node (ref "HDR_B") (pin "59") (pinfunction "59_59") (pintype "passive"))
    )
    (net (code "264") (name "/IO27") (class "Default")
      (node (ref "HDR_B") (pin "61") (pinfunction "61_61") (pintype "passive"))
    )
    (net (code "265") (name "/IO28") (class "Default")
      (node (ref "HDR_B") (pin "63") (pinfunction "63_63") (pintype "passive"))
    )
    (net (code "266") (name "/IO29") (class "Default")
      (node (ref "HDR_B") (pin "65") (pinfunction "65_65") (pintype "passive"))
    )
    (net (code "267") (name "/IO30") (class "Default")
      (node (ref "HDR_B") (pin "67") (pinfunction "67_67") (pintype "passive"))
    )
    (net (code "268") (name "/IO31") (class "Default")
      (node (ref "HDR_B") (pin "69") (pinfunction "69_69") (pintype "passive"))
    )
    (net (code "269") (name "/IO32") (class "Default")
      (node (ref "HDR_B") (pin "71") (pinfunction "71_71") (pintype "passive"))
    )
    (net (code "270") (name "/IO33") (class "Default")
      (node (ref "HDR_B") (pin "73") (pinfunction "73_73") (pintype "passive"))
    )
    (net (code "271") (name "/IO34") (class "Default")
      (node (ref "HDR_B") (pin "75") (pinfunction "75_75") (pintype "passive"))
    )
    (net (code "272") (name "/IO35") (class "Default")
      (node (ref "HDR_B") (pin "77") (pinfunction "77_77") (pintype "passive"))
    )
    (net (code "273") (name "/KBCLOCK") (class "Default")
      (node (ref "HDR_T") (pin "26") (pinfunction "26_26") (pintype "passive"))
    )
    (net (code "274") (name "/KBDATA") (class "Default")
      (node (ref "HDR_T") (pin "28") (pinfunction "28_28") (pintype "passive"))
    )
    (net (code "275") (name "/MOUSECLOCK") (class "Default")
      (node (ref "HDR_T") (pin "30") (pinfunction "30_30") (pintype "passive"))
    )
    (net (code "276") (name "/MOUSEDATA") (class "Default")
      (node (ref "HDR_T") (pin "32") (pinfunction "32_32") (pintype "passive"))
    )
    (net (code "277") (name "/NEXUS_TCK") (class "Default")
      (node (ref "HDR_T") (pin "82") (pinfunction "82_82") (pintype "passive"))
    )
    (net (code "278") (name "/NEXUS_TDI") (class "Default")
      (node (ref "HDR_T") (pin "84") (pinfunction "84_84") (pintype "passive"))
    )
    (net (code "279") (name "/NEXUS_TDO") (class "Default")
      (node (ref "HDR_T") (pin "76") (pinfunction "76_76") (pintype "passive"))
    )
    (net (code "280") (name "/NEXUS_TMS") (class "Default")
      (node (ref "HDR_T") (pin "80") (pinfunction "80_80") (pintype "passive"))
    )
    (net (code "281") (name "/ONE_WIRE_DBID") (class "Default")
      (node (ref "HDR_T") (pin "92") (pinfunction "92_92") (pintype "passive"))
    )
    (net (code "282") (name "/ONE_WIRE_DB_PB") (class "Default")
      (node (ref "HDR_B") (pin "79") (pinfunction "79_79") (pintype "passive"))
    )
    (net (code "283") (name "/ONE_WIRE_PIO1") (class "Default")
      (node (ref "HDR_T") (pin "91") (pinfunction "91_91") (pintype "passive"))
    )
    (net (code "284") (name "/REF_CLK") (class "Default")
      (node (ref "HDR_B") (pin "4") (pinfunction "4_4") (pintype "passive"))
    )
    (net (code "285") (name "/RS232_CTS") (class "Default")
      (node (ref "HDR_T") (pin "22") (pinfunction "22_22") (pintype "passive"))
    )
    (net (code "286") (name "/RS232_RTS") (class "Default")
      (node (ref "HDR_T") (pin "18") (pinfunction "18_18") (pintype "passive"))
    )
    (net (code "287") (name "/RS232_RX") (class "Default")
      (node (ref "HDR_T") (pin "24") (pinfunction "24_24") (pintype "passive"))
    )
    (net (code "288") (name "/RS232_TX") (class "Default")
      (node (ref "HDR_T") (pin "20") (pinfunction "20_20") (pintype "passive"))
    )
    (net (code "289") (name "/SCL") (class "Default")
      (node (ref "HDR_B") (pin "5") (pinfunction "5_5") (pintype "passive"))
    )
    (net (code "290") (name "/SDA") (class "Default")
      (node (ref "HDR_B") (pin "3") (pinfunction "3_3") (pintype "passive"))
    )
    (net (code "291") (name "/SPI_CLK") (class "Default")
      (node (ref "HDR_T") (pin "46") (pinfunction "46_46") (pintype "passive"))
    )
    (net (code "292") (name "/SPI_DIN") (class "Default")
      (node (ref "HDR_T") (pin "44") (pinfunction "44_44") (pintype "passive"))
    )
    (net (code "293") (name "/SPI_DOUT") (class "Default")
      (node (ref "HDR_T") (pin "50") (pinfunction "50_50") (pintype "passive"))
    )
    (net (code "294") (name "/SPI_MODE") (class "Default")
      (node (ref "HDR_T") (pin "52") (pinfunction "52_52") (pintype "passive"))
    )
    (net (code "295") (name "/SPI_SEL") (class "Default")
      (node (ref "HDR_T") (pin "48") (pinfunction "48_48") (pintype "passive"))
    )
    (net (code "296") (name "/SW0") (class "Default")
      (node (ref "HDR_B") (pin "42") (pinfunction "42_42") (pintype "passive"))
    )
    (net (code "297") (name "/SW1") (class "Default")
      (node (ref "HDR_B") (pin "44") (pinfunction "44_44") (pintype "passive"))
    )
    (net (code "298") (name "/SW2") (class "Default")
      (node (ref "HDR_B") (pin "46") (pinfunction "46_46") (pintype "passive"))
    )
    (net (code "299") (name "/SW3") (class "Default")
      (node (ref "HDR_B") (pin "48") (pinfunction "48_48") (pintype "passive"))
    )
    (net (code "300") (name "/SW4") (class "Default")
      (node (ref "HDR_B") (pin "50") (pinfunction "50_50") (pintype "passive"))
    )
    (net (code "303") (name "/USER_LED0") (class "Default")
      (node (ref "HDR_B") (pin "6") (pinfunction "6_6") (pintype "passive"))
    )
    (net (code "304") (name "/USER_LED1") (class "Default")
      (node (ref "HDR_B") (pin "8") (pinfunction "8_8") (pintype "passive"))
    )
    (net (code "305") (name "/USER_LED2") (class "Default")
      (node (ref "HDR_B") (pin "10") (pinfunction "10_10") (pintype "passive"))
    )
    (net (code "306") (name "/USER_LED3") (class "Default")
      (node (ref "HDR_B") (pin "12") (pinfunction "12_12") (pintype "passive"))
    )
    (net (code "307") (name "/USER_LED4") (class "Default")
      (node (ref "HDR_B") (pin "14") (pinfunction "14_14") (pintype "passive"))
    )
    (net (code "308") (name "/USER_LED5") (class "Default")
      (node (ref "HDR_B") (pin "16") (pinfunction "16_16") (pintype "passive"))
    )
    (net (code "309") (name "/USER_LED6") (class "Default")
      (node (ref "HDR_B") (pin "18") (pinfunction "18_18") (pintype "passive"))
    )
    (net (code "310") (name "/USER_LED7") (class "Default")
      (node (ref "HDR_B") (pin "20") (pinfunction "20_20") (pintype "passive"))
    )
    (net (code "328") (name "3V3") (class "Default")
      (node (ref "HDR_B") (pin "94") (pinfunction "94_94") (pintype "passive"))
      (node (ref "HDR_B") (pin "96") (pinfunction "96_96") (pintype "passive"))
      (node (ref "HDR_T") (pin "94") (pinfunction "94_94") (pintype "passive"))
      (node (ref "HDR_T") (pin "96") (pinfunction "96_96") (pintype "passive"))
      (node (ref "NT1") (pin "2") (pinfunction "Net2_2") (pintype "passive"))
    )
    (net (code "329") (name "5V0") (class "Default")
      (node (ref "HDR_B") (pin "97") (pinfunction "97_97") (pintype "passive"))
      (node (ref "HDR_B") (pin "99") (pinfunction "99_99") (pintype "passive"))
      (node (ref "HDR_T") (pin "97") (pinfunction "97_97") (pintype "passive"))
      (node (ref "HDR_T") (pin "99") (pinfunction "99_99") (pintype "passive"))
    )
    (net (code "330") (name "GND") (class "Default")
      (node (ref "HDR_B") (pin "1") (pinfunction "1_1") (pintype "passive"))
      (node (ref "HDR_B") (pin "100") (pinfunction "100_100") (pintype "passive"))
      (node (ref "HDR_B") (pin "98") (pinfunction "98_98") (pintype "passive"))
      (node (ref "HDR_B") (pin "MH1") (pinfunction "MH1_MH1") (pintype "passive"))
      (node (ref "HDR_B") (pin "MH2") (pinfunction "MH2_MH2") (pintype "passive"))
      (node (ref "HDR_B") (pin "MH3") (pinfunction "MH3_MH3") (pintype "passive"))
      (node (ref "HDR_B") (pin "MH4") (pinfunction "MH4_MH4") (pintype "passive"))
      (node (ref "HDR_L") (pin "MH1") (pinfunction "MH1_MH1") (pintype "passive"))
      (node (ref "HDR_L") (pin "MH2") (pinfunction "MH2_MH2") (pintype "passive"))
      (node (ref "HDR_L") (pin "MH3") (pinfunction "MH3_MH3") (pintype "passive"))
      (node (ref "HDR_L") (pin "MH4") (pinfunction "MH4_MH4") (pintype "passive"))
      (node (ref "HDR_T") (pin "1") (pinfunction "1_1") (pintype "passive"))
      (node (ref "HDR_T") (pin "100") (pinfunction "100_100") (pintype "passive"))
      (node (ref "HDR_T") (pin "98") (pinfunction "98_98") (pintype "passive"))
      (node (ref "HDR_T") (pin "MH1") (pinfunction "MH1_MH1") (pintype "passive"))
      (node (ref "HDR_T") (pin "MH2") (pinfunction "MH2_MH2") (pintype "passive"))
      (node (ref "HDR_T") (pin "MH3") (pinfunction "MH3_MH3") (pintype "passive"))
      (node (ref "HDR_T") (pin "MH4") (pinfunction "MH4_MH4") (pintype "passive"))
    )
    (net (code "331") (name "unconnected-(HDR_B-Pad93)") (class "Default")
      (node (ref "HDR_B") (pin "93") (pinfunction "93_93") (pintype "passive+no_connect"))
    )
    (net (code "332") (name "unconnected-(HDR_B-Pad95)") (class "Default")
      (node (ref "HDR_B") (pin "95") (pinfunction "95_95") (pintype "passive+no_connect"))
    )
    (net (code "333") (name "unconnected-(HDR_T-Pad93)") (class "Default")
      (node (ref "HDR_T") (pin "93") (pinfunction "93_93") (pintype "passive+no_connect"))
    )
    (net (code "334") (name "unconnected-(HDR_T-Pad95)") (class "Default")
      (node (ref "HDR_T") (pin "95") (pinfunction "95_95") (pintype "passive+no_connect"))
    )
  )
)
